# CTR_cubesat.net
KiCad netlist of a schematic drawn in EAGLE
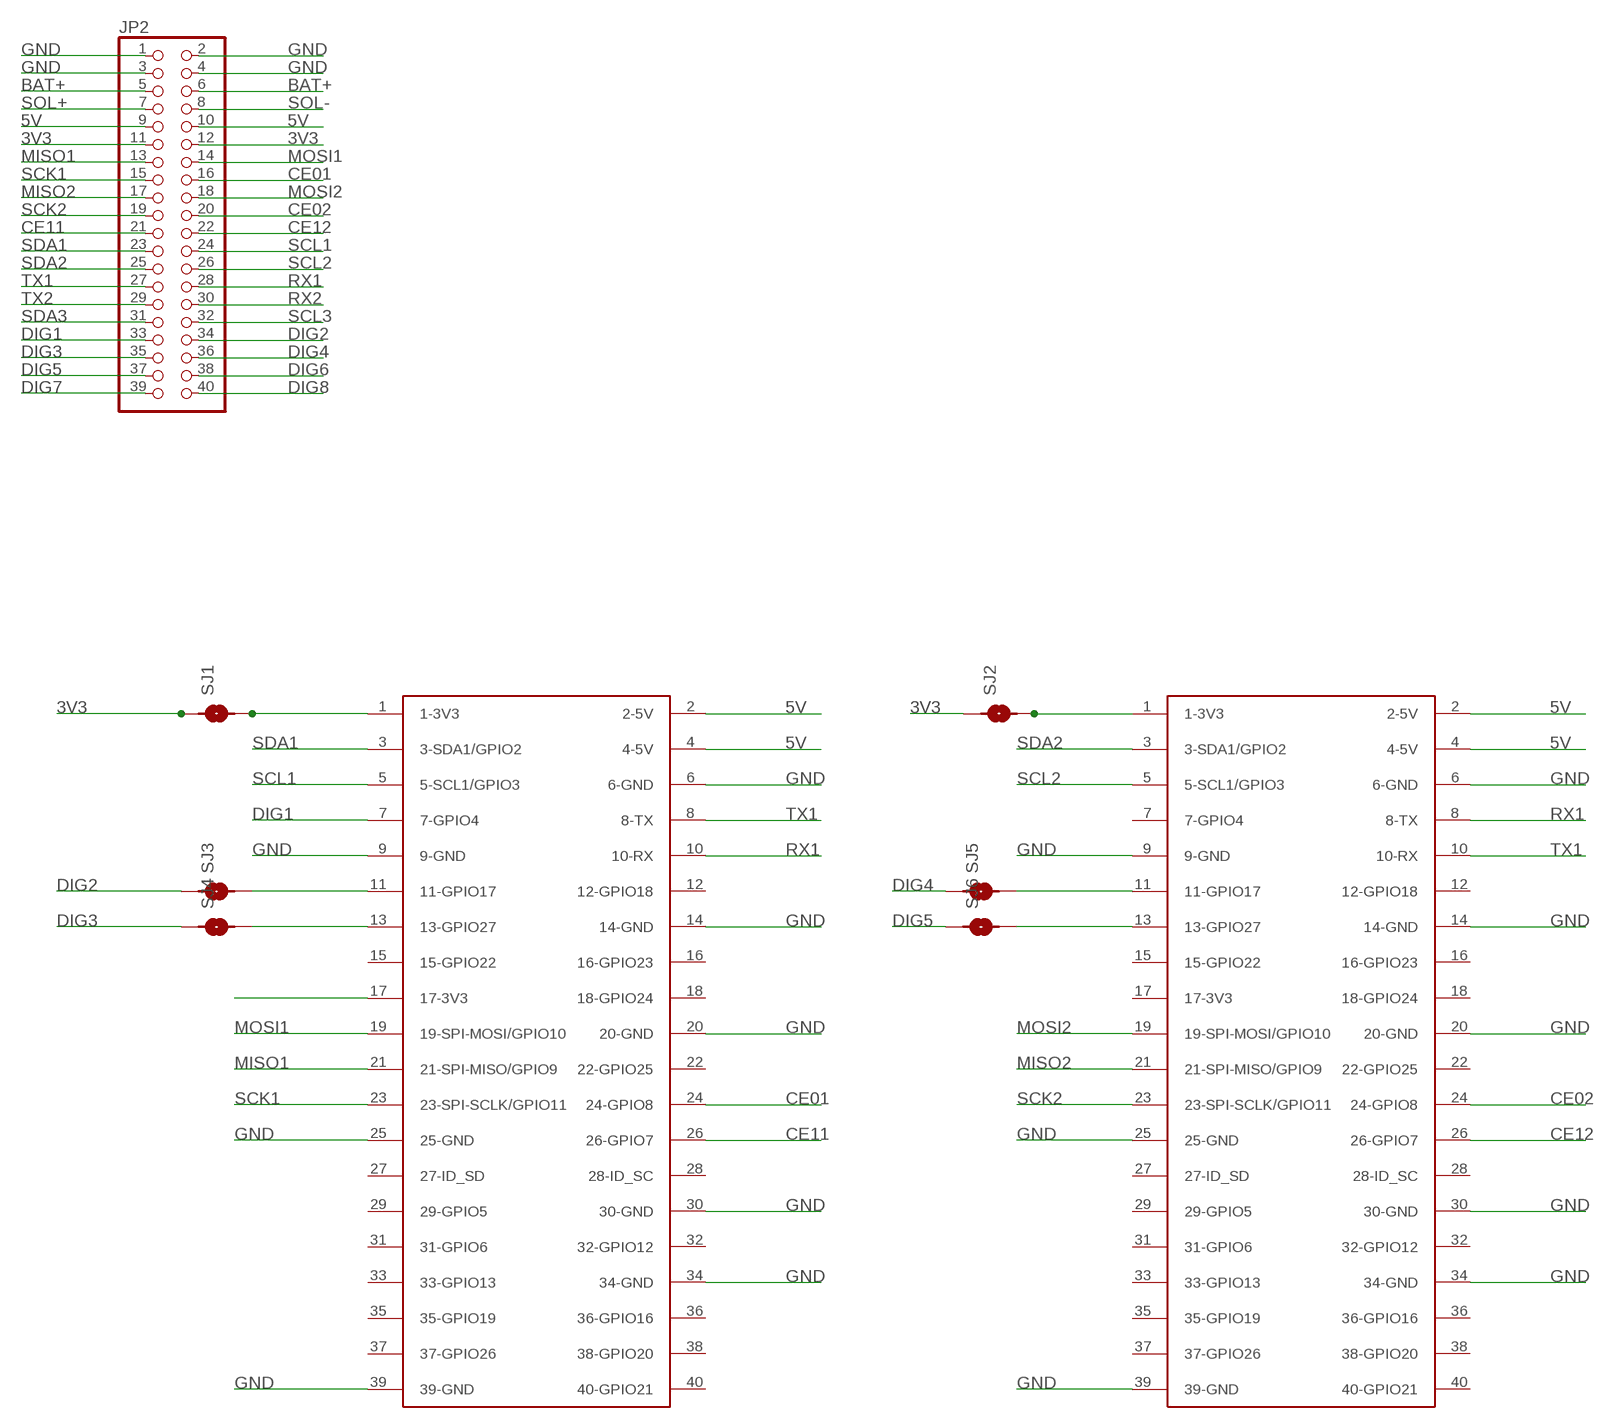
[diagram p0: schematic, sheet 1]

(export (version "E")
  (design (tool "Eeschema 10.0.6"))
  (components
    (comp (ref "JP2")
      (value "PINHD-2X20")
      (footprint "eagle-import:2X20")
      (libsource (lib "eagle-import") (part "PINHD-2X20"))
    )
    (comp (ref "SJ1")
      (value "SMD-JUMPER-2")
      (footprint "eagle-import:SMD-JUMPER-2")
      (libsource (lib "eagle-import") (part "SMD-JUMPER-2"))
    )
    (comp (ref "SJ2")
      (value "SMD-JUMPER-2")
      (footprint "eagle-import:SMD-JUMPER-2")
      (libsource (lib "eagle-import") (part "SMD-JUMPER-2"))
    )
    (comp (ref "SJ3")
      (value "SMD-JUMPER-2")
      (footprint "eagle-import:SMD-JUMPER-2")
      (libsource (lib "eagle-import") (part "SMD-JUMPER-2"))
    )
    (comp (ref "SJ4")
      (value "SMD-JUMPER-2")
      (footprint "eagle-import:SMD-JUMPER-2")
      (libsource (lib "eagle-import") (part "SMD-JUMPER-2"))
    )
    (comp (ref "SJ5")
      (value "SMD-JUMPER-2")
      (footprint "eagle-import:SMD-JUMPER-2")
      (libsource (lib "eagle-import") (part "SMD-JUMPER-2"))
    )
    (comp (ref "SJ6")
      (value "SMD-JUMPER-2")
      (footprint "eagle-import:SMD-JUMPER-2")
      (libsource (lib "eagle-import") (part "SMD-JUMPER-2"))
    )
    (comp (ref "U$1")
      (value "RASPBERRY-PI+PIZERO")
      (footprint "eagle-import:RASPBERRY-PI-ZERO")
      (libsource (lib "eagle-import") (part "RASPBERRY-PI+PIZERO"))
    )
    (comp (ref "U$2")
      (value "RASPBERRY-PI+PIZERO")
      (footprint "eagle-import:RASPBERRY-PI-ZERO")
      (libsource (lib "eagle-import") (part "RASPBERRY-PI+PIZERO"))
    )
  )
  (nets
    (net (code "1") (name "/3V3") (class "Default")
      (node (ref "JP2") (pin "11") (pinfunction "11_11") (pintype "passive"))
      (node (ref "JP2") (pin "12") (pinfunction "12_12") (pintype "passive"))
      (node (ref "SJ1") (pin "1") (pinfunction "1_1") (pintype "passive"))
      (node (ref "SJ2") (pin "1") (pinfunction "1_1") (pintype "passive"))
    )
    (net (code "2") (name "/5V") (class "Default")
      (node (ref "JP2") (pin "10") (pinfunction "10_10") (pintype "passive"))
      (node (ref "JP2") (pin "9") (pinfunction "9_9") (pintype "passive"))
      (node (ref "U$1") (pin "2") (pinfunction "2-5V_2") (pintype "bidirectional"))
      (node (ref "U$1") (pin "4") (pinfunction "4-5V_4") (pintype "bidirectional"))
      (node (ref "U$2") (pin "2") (pinfunction "2-5V_2") (pintype "bidirectional"))
      (node (ref "U$2") (pin "4") (pinfunction "4-5V_4") (pintype "bidirectional"))
    )
    (net (code "3") (name "/BAT+") (class "Default")
      (node (ref "JP2") (pin "5") (pinfunction "5_5") (pintype "passive"))
      (node (ref "JP2") (pin "6") (pinfunction "6_6") (pintype "passive"))
    )
    (net (code "4") (name "/CE01") (class "Default")
      (node (ref "JP2") (pin "16") (pinfunction "16_16") (pintype "passive"))
      (node (ref "U$2") (pin "24") (pinfunction "24-GPIO8_24") (pintype "bidirectional"))
    )
    (net (code "5") (name "/CE02") (class "Default")
      (node (ref "JP2") (pin "20") (pinfunction "20_20") (pintype "passive"))
      (node (ref "U$1") (pin "24") (pinfunction "24-GPIO8_24") (pintype "bidirectional"))
    )
    (net (code "6") (name "/CE11") (class "Default")
      (node (ref "JP2") (pin "21") (pinfunction "21_21") (pintype "passive"))
      (node (ref "U$2") (pin "26") (pinfunction "26-GPIO7_26") (pintype "bidirectional"))
    )
    (net (code "7") (name "/CE12") (class "Default")
      (node (ref "JP2") (pin "22") (pinfunction "22_22") (pintype "passive"))
      (node (ref "U$1") (pin "26") (pinfunction "26-GPIO7_26") (pintype "bidirectional"))
    )
    (net (code "8") (name "/DIG1") (class "Default")
      (node (ref "JP2") (pin "33") (pinfunction "33_33") (pintype "passive"))
      (node (ref "U$2") (pin "7") (pinfunction "7-GPIO4_7") (pintype "bidirectional"))
    )
    (net (code "9") (name "/DIG2") (class "Default")
      (node (ref "JP2") (pin "34") (pinfunction "34_34") (pintype "passive"))
      (node (ref "SJ3") (pin "1") (pinfunction "1_1") (pintype "passive"))
    )
    (net (code "10") (name "/DIG3") (class "Default")
      (node (ref "JP2") (pin "35") (pinfunction "35_35") (pintype "passive"))
      (node (ref "SJ4") (pin "1") (pinfunction "1_1") (pintype "passive"))
    )
    (net (code "11") (name "/DIG4") (class "Default")
      (node (ref "JP2") (pin "36") (pinfunction "36_36") (pintype "passive"))
      (node (ref "SJ5") (pin "1") (pinfunction "1_1") (pintype "passive"))
    )
    (net (code "12") (name "/DIG5") (class "Default")
      (node (ref "JP2") (pin "37") (pinfunction "37_37") (pintype "passive"))
      (node (ref "SJ6") (pin "1") (pinfunction "1_1") (pintype "passive"))
    )
    (net (code "13") (name "/DIG6") (class "Default")
      (node (ref "JP2") (pin "38") (pinfunction "38_38") (pintype "passive"))
    )
    (net (code "14") (name "/DIG7") (class "Default")
      (node (ref "JP2") (pin "39") (pinfunction "39_39") (pintype "passive"))
    )
    (net (code "15") (name "/DIG8") (class "Default")
      (node (ref "JP2") (pin "40") (pinfunction "40_40") (pintype "passive"))
    )
    (net (code "16") (name "/GND") (class "Default")
      (node (ref "JP2") (pin "1") (pinfunction "1_1") (pintype "passive"))
      (node (ref "JP2") (pin "2") (pinfunction "2_2") (pintype "passive"))
      (node (ref "JP2") (pin "3") (pinfunction "3_3") (pintype "passive"))
      (node (ref "JP2") (pin "4") (pinfunction "4_4") (pintype "passive"))
      (node (ref "U$1") (pin "14") (pinfunction "14-GND_14") (pintype "bidirectional"))
      (node (ref "U$1") (pin "20") (pinfunction "20-GND_20") (pintype "bidirectional"))
      (node (ref "U$1") (pin "25") (pinfunction "25-GND_25") (pintype "bidirectional"))
      (node (ref "U$1") (pin "30") (pinfunction "30-GND_30") (pintype "bidirectional"))
      (node (ref "U$1") (pin "34") (pinfunction "34-GND_34") (pintype "bidirectional"))
      (node (ref "U$1") (pin "39") (pinfunction "39-GND_39") (pintype "bidirectional"))
      (node (ref "U$1") (pin "6") (pinfunction "6-GND_6") (pintype "bidirectional"))
      (node (ref "U$1") (pin "9") (pinfunction "9-GND_9") (pintype "bidirectional"))
      (node (ref "U$2") (pin "14") (pinfunction "14-GND_14") (pintype "bidirectional"))
      (node (ref "U$2") (pin "20") (pinfunction "20-GND_20") (pintype "bidirectional"))
      (node (ref "U$2") (pin "25") (pinfunction "25-GND_25") (pintype "bidirectional"))
      (node (ref "U$2") (pin "30") (pinfunction "30-GND_30") (pintype "bidirectional"))
      (node (ref "U$2") (pin "34") (pinfunction "34-GND_34") (pintype "bidirectional"))
      (node (ref "U$2") (pin "39") (pinfunction "39-GND_39") (pintype "bidirectional"))
      (node (ref "U$2") (pin "6") (pinfunction "6-GND_6") (pintype "bidirectional"))
      (node (ref "U$2") (pin "9") (pinfunction "9-GND_9") (pintype "bidirectional"))
    )
    (net (code "17") (name "/MISO1") (class "Default")
      (node (ref "JP2") (pin "13") (pinfunction "13_13") (pintype "passive"))
      (node (ref "U$2") (pin "21") (pinfunction "21-SPI-MISO/GPIO9_21") (pintype "bidirectional"))
    )
    (net (code "18") (name "/MISO2") (class "Default")
      (node (ref "JP2") (pin "17") (pinfunction "17_17") (pintype "passive"))
      (node (ref "U$1") (pin "21") (pinfunction "21-SPI-MISO/GPIO9_21") (pintype "bidirectional"))
    )
    (net (code "19") (name "/MOSI1") (class "Default")
      (node (ref "JP2") (pin "14") (pinfunction "14_14") (pintype "passive"))
      (node (ref "U$2") (pin "19") (pinfunction "19-SPI-MOSI/GPIO10_19") (pintype "bidirectional"))
    )
    (net (code "20") (name "/MOSI2") (class "Default")
      (node (ref "JP2") (pin "18") (pinfunction "18_18") (pintype "passive"))
      (node (ref "U$1") (pin "19") (pinfunction "19-SPI-MOSI/GPIO10_19") (pintype "bidirectional"))
    )
    (net (code "21") (name "/RX1") (class "Default")
      (node (ref "JP2") (pin "28") (pinfunction "28_28") (pintype "passive"))
      (node (ref "U$1") (pin "8") (pinfunction "8-TX_8") (pintype "bidirectional"))
      (node (ref "U$2") (pin "10") (pinfunction "10-RX_10") (pintype "bidirectional"))
    )
    (net (code "22") (name "/RX2") (class "Default")
      (node (ref "JP2") (pin "30") (pinfunction "30_30") (pintype "passive"))
    )
    (net (code "23") (name "/SCK1") (class "Default")
      (node (ref "JP2") (pin "15") (pinfunction "15_15") (pintype "passive"))
      (node (ref "U$2") (pin "23") (pinfunction "23-SPI-SCLK/GPIO11_23") (pintype "bidirectional"))
    )
    (net (code "24") (name "/SCK2") (class "Default")
      (node (ref "JP2") (pin "19") (pinfunction "19_19") (pintype "passive"))
      (node (ref "U$1") (pin "23") (pinfunction "23-SPI-SCLK/GPIO11_23") (pintype "bidirectional"))
    )
    (net (code "25") (name "/SCL1") (class "Default")
      (node (ref "JP2") (pin "24") (pinfunction "24_24") (pintype "passive"))
      (node (ref "U$2") (pin "5") (pinfunction "5-SCL1/GPIO3_5") (pintype "bidirectional"))
    )
    (net (code "26") (name "/SCL2") (class "Default")
      (node (ref "JP2") (pin "26") (pinfunction "26_26") (pintype "passive"))
      (node (ref "U$1") (pin "5") (pinfunction "5-SCL1/GPIO3_5") (pintype "bidirectional"))
    )
    (net (code "27") (name "/SCL3") (class "Default")
      (node (ref "JP2") (pin "32") (pinfunction "32_32") (pintype "passive"))
    )
    (net (code "28") (name "/SDA1") (class "Default")
      (node (ref "JP2") (pin "23") (pinfunction "23_23") (pintype "passive"))
      (node (ref "U$2") (pin "3") (pinfunction "3-SDA1/GPIO2_3") (pintype "bidirectional"))
    )
    (net (code "29") (name "/SDA2") (class "Default")
      (node (ref "JP2") (pin "25") (pinfunction "25_25") (pintype "passive"))
      (node (ref "U$1") (pin "3") (pinfunction "3-SDA1/GPIO2_3") (pintype "bidirectional"))
    )
    (net (code "30") (name "/SDA3") (class "Default")
      (node (ref "JP2") (pin "31") (pinfunction "31_31") (pintype "passive"))
    )
    (net (code "31") (name "/SOL+") (class "Default")
      (node (ref "JP2") (pin "7") (pinfunction "7_7") (pintype "passive"))
    )
    (net (code "32") (name "/SOL-") (class "Default")
      (node (ref "JP2") (pin "8") (pinfunction "8_8") (pintype "passive"))
    )
    (net (code "33") (name "/TX1") (class "Default")
      (node (ref "JP2") (pin "27") (pinfunction "27_27") (pintype "passive"))
      (node (ref "U$1") (pin "10") (pinfunction "10-RX_10") (pintype "bidirectional"))
      (node (ref "U$2") (pin "8") (pinfunction "8-TX_8") (pintype "bidirectional"))
    )
    (net (code "34") (name "/TX2") (class "Default")
      (node (ref "JP2") (pin "29") (pinfunction "29_29") (pintype "passive"))
    )
    (net (code "35") (name "Net-(U$1-1-3V3)") (class "Default")
      (node (ref "SJ2") (pin "2") (pinfunction "2_2") (pintype "passive"))
      (node (ref "U$1") (pin "1") (pinfunction "1-3V3_1") (pintype "bidirectional"))
    )
    (net (code "36") (name "Net-(U$1-11-GPIO17)") (class "Default")
      (node (ref "SJ5") (pin "2") (pinfunction "2_2") (pintype "passive"))
      (node (ref "U$1") (pin "11") (pinfunction "11-GPIO17_11") (pintype "bidirectional"))
    )
    (net (code "37") (name "Net-(U$1-13-GPIO27)") (class "Default")
      (node (ref "SJ6") (pin "2") (pinfunction "2_2") (pintype "passive"))
      (node (ref "U$1") (pin "13") (pinfunction "13-GPIO27_13") (pintype "bidirectional"))
    )
    (net (code "38") (name "Net-(U$2-1-3V3)") (class "Default")
      (node (ref "SJ1") (pin "2") (pinfunction "2_2") (pintype "passive"))
      (node (ref "U$2") (pin "1") (pinfunction "1-3V3_1") (pintype "bidirectional"))
    )
    (net (code "39") (name "Net-(U$2-11-GPIO17)") (class "Default")
      (node (ref "SJ3") (pin "2") (pinfunction "2_2") (pintype "passive"))
      (node (ref "U$2") (pin "11") (pinfunction "11-GPIO17_11") (pintype "bidirectional"))
    )
    (net (code "40") (name "Net-(U$2-13-GPIO27)") (class "Default")
      (node (ref "SJ4") (pin "2") (pinfunction "2_2") (pintype "passive"))
      (node (ref "U$2") (pin "13") (pinfunction "13-GPIO27_13") (pintype "bidirectional"))
    )
    (net (code "41") (name "unconnected-(U$1-7-GPIO4-Pad7)") (class "Default")
      (node (ref "U$1") (pin "7") (pinfunction "7-GPIO4_7") (pintype "bidirectional"))
    )
    (net (code "42") (name "unconnected-(U$1-12-GPIO18-Pad12)") (class "Default")
      (node (ref "U$1") (pin "12") (pinfunction "12-GPIO18_12") (pintype "bidirectional"))
    )
    (net (code "43") (name "unconnected-(U$1-15-GPIO22-Pad15)") (class "Default")
      (node (ref "U$1") (pin "15") (pinfunction "15-GPIO22_15") (pintype "bidirectional"))
    )
    (net (code "44") (name "unconnected-(U$1-16-GPIO23-Pad16)") (class "Default")
      (node (ref "U$1") (pin "16") (pinfunction "16-GPIO23_16") (pintype "bidirectional"))
    )
    (net (code "45") (name "unconnected-(U$1-17-3V3-Pad17)") (class "Default")
      (node (ref "U$1") (pin "17") (pinfunction "17-3V3_17") (pintype "bidirectional"))
    )
    (net (code "46") (name "unconnected-(U$1-18-GPIO24-Pad18)") (class "Default")
      (node (ref "U$1") (pin "18") (pinfunction "18-GPIO24_18") (pintype "bidirectional"))
    )
    (net (code "47") (name "unconnected-(U$1-22-GPIO25-Pad22)") (class "Default")
      (node (ref "U$1") (pin "22") (pinfunction "22-GPIO25_22") (pintype "bidirectional"))
    )
    (net (code "48") (name "unconnected-(U$1-27-ID_SD-Pad27)") (class "Default")
      (node (ref "U$1") (pin "27") (pinfunction "27-ID_SD_27") (pintype "bidirectional"))
    )
    (net (code "49") (name "unconnected-(U$1-28-ID_SC-Pad28)") (class "Default")
      (node (ref "U$1") (pin "28") (pinfunction "28-ID_SC_28") (pintype "bidirectional"))
    )
    (net (code "50") (name "unconnected-(U$1-29-GPIO5-Pad29)") (class "Default")
      (node (ref "U$1") (pin "29") (pinfunction "29-GPIO5_29") (pintype "bidirectional"))
    )
    (net (code "51") (name "unconnected-(U$1-31-GPIO6-Pad31)") (class "Default")
      (node (ref "U$1") (pin "31") (pinfunction "31-GPIO6_31") (pintype "bidirectional"))
    )
    (net (code "52") (name "unconnected-(U$1-32-GPIO12-Pad32)") (class "Default")
      (node (ref "U$1") (pin "32") (pinfunction "32-GPIO12_32") (pintype "bidirectional"))
    )
    (net (code "53") (name "unconnected-(U$1-33-GPIO13-Pad33)") (class "Default")
      (node (ref "U$1") (pin "33") (pinfunction "33-GPIO13_33") (pintype "bidirectional"))
    )
    (net (code "54") (name "unconnected-(U$1-35-GPIO19-Pad35)") (class "Default")
      (node (ref "U$1") (pin "35") (pinfunction "35-GPIO19_35") (pintype "bidirectional"))
    )
    (net (code "55") (name "unconnected-(U$1-36-GPIO16-Pad36)") (class "Default")
      (node (ref "U$1") (pin "36") (pinfunction "36-GPIO16_36") (pintype "bidirectional"))
    )
    (net (code "56") (name "unconnected-(U$1-37-GPIO26-Pad37)") (class "Default")
      (node (ref "U$1") (pin "37") (pinfunction "37-GPIO26_37") (pintype "bidirectional"))
    )
    (net (code "57") (name "unconnected-(U$1-38-GPIO20-Pad38)") (class "Default")
      (node (ref "U$1") (pin "38") (pinfunction "38-GPIO20_38") (pintype "bidirectional"))
    )
    (net (code "58") (name "unconnected-(U$1-40-GPIO21-Pad40)") (class "Default")
      (node (ref "U$1") (pin "40") (pinfunction "40-GPIO21_40") (pintype "bidirectional"))
    )
    (net (code "59") (name "unconnected-(U$2-12-GPIO18-Pad12)") (class "Default")
      (node (ref "U$2") (pin "12") (pinfunction "12-GPIO18_12") (pintype "bidirectional"))
    )
    (net (code "60") (name "unconnected-(U$2-15-GPIO22-Pad15)") (class "Default")
      (node (ref "U$2") (pin "15") (pinfunction "15-GPIO22_15") (pintype "bidirectional"))
    )
    (net (code "61") (name "unconnected-(U$2-16-GPIO23-Pad16)") (class "Default")
      (node (ref "U$2") (pin "16") (pinfunction "16-GPIO23_16") (pintype "bidirectional"))
    )
    (net (code "62") (name "unconnected-(U$2-17-3V3-Pad17)") (class "Default")
      (node (ref "U$2") (pin "17") (pinfunction "17-3V3_17") (pintype "bidirectional"))
    )
    (net (code "63") (name "unconnected-(U$2-18-GPIO24-Pad18)") (class "Default")
      (node (ref "U$2") (pin "18") (pinfunction "18-GPIO24_18") (pintype "bidirectional"))
    )
    (net (code "64") (name "unconnected-(U$2-22-GPIO25-Pad22)") (class "Default")
      (node (ref "U$2") (pin "22") (pinfunction "22-GPIO25_22") (pintype "bidirectional"))
    )
    (net (code "65") (name "unconnected-(U$2-27-ID_SD-Pad27)") (class "Default")
      (node (ref "U$2") (pin "27") (pinfunction "27-ID_SD_27") (pintype "bidirectional"))
    )
    (net (code "66") (name "unconnected-(U$2-28-ID_SC-Pad28)") (class "Default")
      (node (ref "U$2") (pin "28") (pinfunction "28-ID_SC_28") (pintype "bidirectional"))
    )
    (net (code "67") (name "unconnected-(U$2-29-GPIO5-Pad29)") (class "Default")
      (node (ref "U$2") (pin "29") (pinfunction "29-GPIO5_29") (pintype "bidirectional"))
    )
    (net (code "68") (name "unconnected-(U$2-31-GPIO6-Pad31)") (class "Default")
      (node (ref "U$2") (pin "31") (pinfunction "31-GPIO6_31") (pintype "bidirectional"))
    )
    (net (code "69") (name "unconnected-(U$2-32-GPIO12-Pad32)") (class "Default")
      (node (ref "U$2") (pin "32") (pinfunction "32-GPIO12_32") (pintype "bidirectional"))
    )
    (net (code "70") (name "unconnected-(U$2-33-GPIO13-Pad33)") (class "Default")
      (node (ref "U$2") (pin "33") (pinfunction "33-GPIO13_33") (pintype "bidirectional"))
    )
    (net (code "71") (name "unconnected-(U$2-35-GPIO19-Pad35)") (class "Default")
      (node (ref "U$2") (pin "35") (pinfunction "35-GPIO19_35") (pintype "bidirectional"))
    )
    (net (code "72") (name "unconnected-(U$2-36-GPIO16-Pad36)") (class "Default")
      (node (ref "U$2") (pin "36") (pinfunction "36-GPIO16_36") (pintype "bidirectional"))
    )
    (net (code "73") (name "unconnected-(U$2-37-GPIO26-Pad37)") (class "Default")
      (node (ref "U$2") (pin "37") (pinfunction "37-GPIO26_37") (pintype "bidirectional"))
    )
    (net (code "74") (name "unconnected-(U$2-38-GPIO20-Pad38)") (class "Default")
      (node (ref "U$2") (pin "38") (pinfunction "38-GPIO20_38") (pintype "bidirectional"))
    )
    (net (code "75") (name "unconnected-(U$2-40-GPIO21-Pad40)") (class "Default")
      (node (ref "U$2") (pin "40") (pinfunction "40-GPIO21_40") (pintype "bidirectional"))
    )
  )
)
